# 12VAC-DC-v6.net
KiCad netlist of a schematic drawn in EAGLE
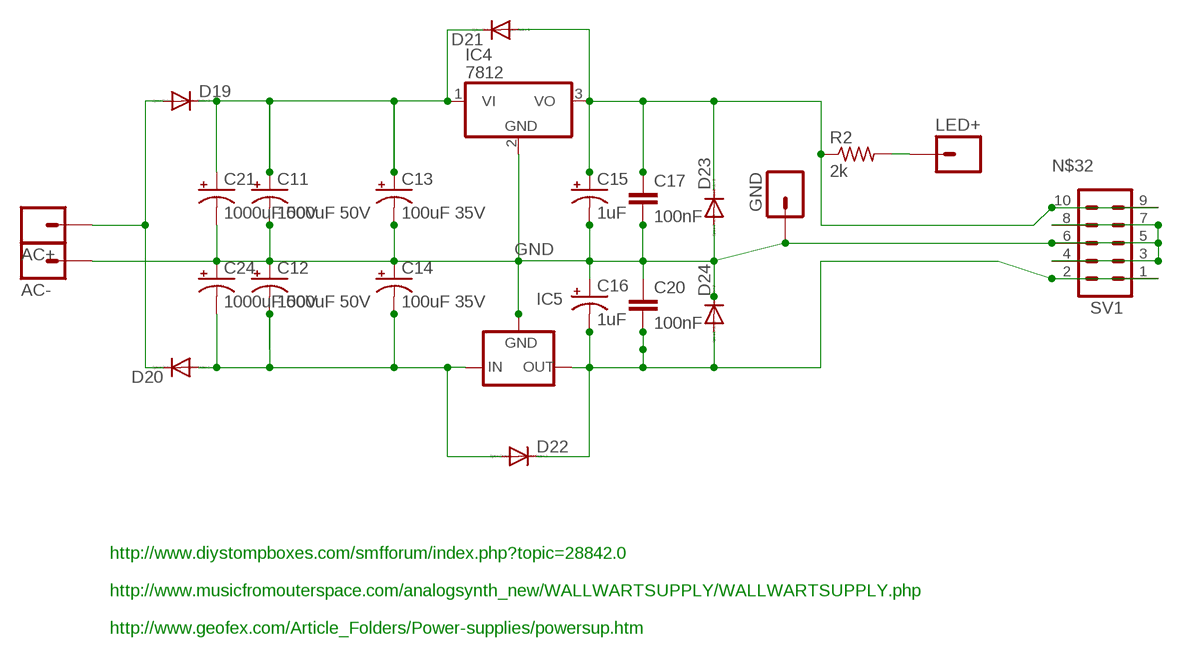
[diagram p0: schematic, sheet 1]

(export (version "E")
  (design (tool "Eeschema 10.0.6"))
  (components
    (comp (ref "C11")
      (value "1000uF 50V")
      (footprint "eagle-import:E5-13")
      (libsource (lib "eagle-import") (part "CPOL-USE5-13"))
    )
    (comp (ref "C12")
      (value "1000uF 50V")
      (footprint "eagle-import:E5-13")
      (libsource (lib "eagle-import") (part "CPOL-USE5-13"))
    )
    (comp (ref "C13")
      (value "100uF 35V")
      (footprint "eagle-import:E2,5-6")
      (libsource (lib "eagle-import") (part "CPOL-USE2.5-6"))
    )
    (comp (ref "C14")
      (value "100uF 35V")
      (footprint "eagle-import:E2,5-6")
      (libsource (lib "eagle-import") (part "CPOL-USE2.5-6"))
    )
    (comp (ref "C15")
      (value "1uF")
      (footprint "eagle-import:E2,5-5")
      (libsource (lib "eagle-import") (part "CPOL-USE2.5-5"))
    )
    (comp (ref "C16")
      (value "1uF")
      (footprint "eagle-import:E2,5-5")
      (libsource (lib "eagle-import") (part "CPOL-USE2.5-5"))
    )
    (comp (ref "C17")
      (value "100nF")
      (footprint "eagle-import:C025-024X044")
      (libsource (lib "eagle-import") (part "C-EU025-024X044"))
    )
    (comp (ref "C20")
      (value "100nF")
      (footprint "eagle-import:C025-024X044")
      (libsource (lib "eagle-import") (part "C-EU025-024X044"))
    )
    (comp (ref "C21")
      (value "1000uF 50V")
      (footprint "eagle-import:E5-13")
      (libsource (lib "eagle-import") (part "CPOL-USE5-13"))
    )
    (comp (ref "C24")
      (value "1000uF 50V")
      (footprint "eagle-import:E5-13")
      (libsource (lib "eagle-import") (part "CPOL-USE5-13"))
    )
    (comp (ref "D19")
      (value "DIODE-D-7.5")
      (footprint "eagle-import:D-7.5")
      (libsource (lib "eagle-import") (part "DIODE-D-7.5"))
    )
    (comp (ref "D20")
      (value "DIODE-D-7.5")
      (footprint "eagle-import:D-7.5")
      (libsource (lib "eagle-import") (part "DIODE-D-7.5"))
    )
    (comp (ref "D21")
      (value "DIODE-D-5")
      (footprint "eagle-import:D-5")
      (libsource (lib "eagle-import") (part "DIODE-D-5"))
    )
    (comp (ref "D22")
      (value "DIODE-D-5")
      (footprint "eagle-import:D-5")
      (libsource (lib "eagle-import") (part "DIODE-D-5"))
    )
    (comp (ref "D23")
      (value "DIODE-D-2.5")
      (footprint "eagle-import:D-2.5")
      (libsource (lib "eagle-import") (part "DIODE-D-2.5"))
    )
    (comp (ref "D24")
      (value "DIODE-D-5")
      (footprint "eagle-import:D-5")
      (libsource (lib "eagle-import") (part "DIODE-D-5"))
    )
    (comp (ref "IC4")
      (value "7812")
      (footprint "eagle-import:TO220V")
      (libsource (lib "eagle-import") (part "78TV12"))
    )
    (comp (ref "IC5")
      (value "79XXS")
      (footprint "eagle-import:79XXS")
      (libsource (lib "eagle-import") (part "79XXS"))
    )
    (comp (ref "JP6")
      (value "AC+")
      (footprint "eagle-import:1X01_LONGPAD")
      (libsource (lib "eagle-import") (part "M01PTH_LONGPAD"))
    )
    (comp (ref "JP22")
      (value "AC-")
      (footprint "eagle-import:1X01_LONGPAD")
      (libsource (lib "eagle-import") (part "M01PTH_LONGPAD"))
    )
    (comp (ref "JP25")
      (value "GND")
      (footprint "eagle-import:1X01_LONGPAD")
      (libsource (lib "eagle-import") (part "M01PTH_LONGPAD"))
    )
    (comp (ref "JP26")
      (value "LED+")
      (footprint "eagle-import:1X01_LONGPAD")
      (libsource (lib "eagle-import") (part "M01PTH_LONGPAD"))
    )
    (comp (ref "R2")
      (value "2k")
      (footprint "eagle-import:0204V")
      (libsource (lib "eagle-import") (part "R-US_0204/2V"))
    )
    (comp (ref "SV1")
      (value "M05X2SHD")
      (footprint "eagle-import:2X5-SHROUDED")
      (libsource (lib "eagle-import") (part "M05X2SHD"))
    )
  )
  (nets
    (net (code "1") (name "/GND") (class "Default")
      (node (ref "C11") (pin "-") (pinfunction "-_-") (pintype "passive"))
      (node (ref "C12") (pin "+") (pinfunction "+_+") (pintype "passive"))
      (node (ref "C13") (pin "-") (pinfunction "-_-") (pintype "passive"))
      (node (ref "C14") (pin "+") (pinfunction "+_+") (pintype "passive"))
      (node (ref "C15") (pin "-") (pinfunction "-_-") (pintype "passive"))
      (node (ref "C16") (pin "+") (pinfunction "+_+") (pintype "passive"))
      (node (ref "C17") (pin "2") (pinfunction "2_2") (pintype "passive"))
      (node (ref "C20") (pin "1") (pinfunction "1_1") (pintype "passive"))
      (node (ref "C21") (pin "-") (pinfunction "-_-") (pintype "passive"))
      (node (ref "C24") (pin "+") (pinfunction "+_+") (pintype "passive"))
      (node (ref "D23") (pin "A") (pinfunction "A_A") (pintype "passive"))
      (node (ref "D24") (pin "C") (pinfunction "C_C") (pintype "passive"))
      (node (ref "IC4") (pin "2") (pinfunction "GND_2") (pintype "passive"))
      (node (ref "IC5") (pin "GND") (pinfunction "GND_GND") (pintype "input"))
      (node (ref "JP22") (pin "1") (pinfunction "1_1") (pintype "passive"))
      (node (ref "JP25") (pin "1") (pinfunction "1_1") (pintype "passive"))
      (node (ref "SV1") (pin "3") (pinfunction "3_3") (pintype "passive"))
      (node (ref "SV1") (pin "4") (pinfunction "4_4") (pintype "passive"))
      (node (ref "SV1") (pin "5") (pinfunction "5_5") (pintype "passive"))
      (node (ref "SV1") (pin "6") (pinfunction "6_6") (pintype "passive"))
      (node (ref "SV1") (pin "7") (pinfunction "7_7") (pintype "passive"))
      (node (ref "SV1") (pin "8") (pinfunction "8_8") (pintype "passive"))
    )
    (net (code "2") (name "/N$32") (class "Default")
      (node (ref "C15") (pin "+") (pinfunction "+_+") (pintype "passive"))
      (node (ref "C17") (pin "1") (pinfunction "1_1") (pintype "passive"))
      (node (ref "D21") (pin "A") (pinfunction "A_A") (pintype "passive"))
      (node (ref "D23") (pin "C") (pinfunction "C_C") (pintype "passive"))
      (node (ref "IC4") (pin "3") (pinfunction "VO_3") (pintype "passive"))
      (node (ref "R2") (pin "1") (pinfunction "1_1") (pintype "passive"))
      (node (ref "SV1") (pin "10") (pinfunction "10_10") (pintype "passive"))
      (node (ref "SV1") (pin "9") (pinfunction "9_9") (pintype "passive"))
    )
    (net (code "3") (name "Net-(C12-Pad-)") (class "Default")
      (node (ref "C12") (pin "-") (pinfunction "-_-") (pintype "passive"))
      (node (ref "C14") (pin "-") (pinfunction "-_-") (pintype "passive"))
      (node (ref "C24") (pin "-") (pinfunction "-_-") (pintype "passive"))
      (node (ref "D20") (pin "A") (pinfunction "A_A") (pintype "passive"))
      (node (ref "D22") (pin "A") (pinfunction "A_A") (pintype "passive"))
      (node (ref "IC5") (pin "IN") (pinfunction "IN_IN") (pintype "input"))
    )
    (net (code "4") (name "Net-(C16-Pad-)") (class "Default")
      (node (ref "C16") (pin "-") (pinfunction "-_-") (pintype "passive"))
      (node (ref "C20") (pin "2") (pinfunction "2_2") (pintype "passive"))
      (node (ref "D22") (pin "C") (pinfunction "C_C") (pintype "passive"))
      (node (ref "D24") (pin "A") (pinfunction "A_A") (pintype "passive"))
      (node (ref "IC5") (pin "OUT") (pinfunction "OUT_OUT") (pintype "passive"))
      (node (ref "SV1") (pin "1") (pinfunction "1_1") (pintype "passive"))
      (node (ref "SV1") (pin "2") (pinfunction "2_2") (pintype "passive"))
    )
    (net (code "5") (name "Net-(D19-PadA)") (class "Default")
      (node (ref "D19") (pin "A") (pinfunction "A_A") (pintype "passive"))
      (node (ref "D20") (pin "C") (pinfunction "C_C") (pintype "passive"))
      (node (ref "JP6") (pin "1") (pinfunction "1_1") (pintype "passive"))
    )
    (net (code "6") (name "Net-(IC4-VI)") (class "Default")
      (node (ref "C11") (pin "+") (pinfunction "+_+") (pintype "passive"))
      (node (ref "C13") (pin "+") (pinfunction "+_+") (pintype "passive"))
      (node (ref "C21") (pin "+") (pinfunction "+_+") (pintype "passive"))
      (node (ref "D19") (pin "C") (pinfunction "C_C") (pintype "passive"))
      (node (ref "D21") (pin "C") (pinfunction "C_C") (pintype "passive"))
      (node (ref "IC4") (pin "1") (pinfunction "VI_1") (pintype "input"))
    )
    (net (code "7") (name "Net-(JP26-Pad1)") (class "Default")
      (node (ref "JP26") (pin "1") (pinfunction "1_1") (pintype "passive"))
      (node (ref "R2") (pin "2") (pinfunction "2_2") (pintype "passive"))
    )
  )
)
